# TLE5012B.net
KiCad netlist of a schematic drawn in Altium Designer
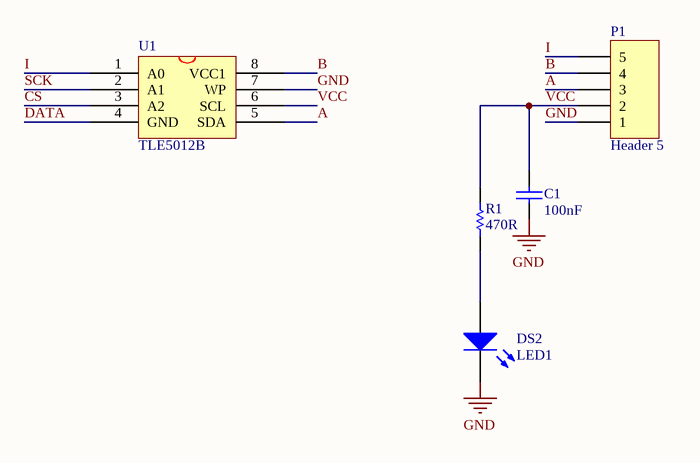
[diagram p0: TLE5012B.SchDoc]

(export (version "E")
  (design (tool "Eeschema 10.0.6"))
  (components
    (comp (ref "C1")
      (value "100nF")
      (footprint "C 0402")
      (description "Capacitor")
      (fields (field (name "PUBLISHER") "Altium Limited"))
      (libsource (lib "Miscellaneous Devices") (part "CAP"))
    )
    (comp (ref "DS2")
      (value "LED1")
      (footprint "SMDLED")
      (description "Typical RED, GREEN, YELLOW, AMBER GaAs LED")
      (fields (field (name "PUBLISHER") "Altium Limited"))
      (libsource (lib "EXPLORER") (part "LED2"))
    )
    (comp (ref "P1")
      (value "Header 5")
      (footprint "PH1.25_5")
      (description "Header, 5-Pin")
      (fields (field (name "PUBLISHER") "Altium Limited"))
      (libsource (lib "Miscellaneous Connectors") (part "Header 5"))
    )
    (comp (ref "R1")
      (value "470R")
      (footprint "R 0402")
      (description "0603")
      (libsource (lib "stm32f429i") (part "Res2"))
    )
    (comp (ref "U1") (value "TLE5012B") (footprint "SOP-8") (libsource (lib "EXPLORER") (part "24C256")))
  )
  (nets
    (net (code "1") (name "/A") (class "Default")
      (node (ref "P1") (pin "3") (pinfunction "3_3") (pintype "passive"))
      (node (ref "U1") (pin "5") (pinfunction "SDA_5") (pintype "passive"))
    )
    (net (code "2") (name "/B") (class "Default")
      (node (ref "P1") (pin "4") (pinfunction "4_4") (pintype "passive"))
      (node (ref "U1") (pin "8") (pinfunction "VCC1_8") (pintype "passive"))
    )
    (net (code "3") (name "/CS") (class "Default")
      (node (ref "U1") (pin "3") (pinfunction "A2_3") (pintype "passive"))
    )
    (net (code "4") (name "/DATA") (class "Default")
      (node (ref "U1") (pin "4") (pinfunction "GND_4") (pintype "passive"))
    )
    (net (code "5") (name "/I") (class "Default")
      (node (ref "P1") (pin "5") (pinfunction "5_5") (pintype "passive"))
      (node (ref "U1") (pin "1") (pinfunction "A0_1") (pintype "passive"))
    )
    (net (code "6") (name "/SCK") (class "Default")
      (node (ref "U1") (pin "2") (pinfunction "A1_2") (pintype "passive"))
    )
    (net (code "7") (name "/VCC") (class "Default")
      (node (ref "C1") (pin "1") (pinfunction "1_1") (pintype "passive"))
      (node (ref "P1") (pin "2") (pinfunction "2_2") (pintype "passive"))
      (node (ref "R1") (pin "1") (pinfunction "1_1") (pintype "passive"))
      (node (ref "U1") (pin "6") (pinfunction "SCL_6") (pintype "passive"))
    )
    (net (code "8") (name "GND") (class "Default")
      (node (ref "C1") (pin "2") (pinfunction "2_2") (pintype "passive"))
      (node (ref "DS2") (pin "2") (pinfunction "K_2") (pintype "passive"))
      (node (ref "P1") (pin "1") (pinfunction "1_1") (pintype "passive"))
      (node (ref "U1") (pin "7") (pinfunction "WP_7") (pintype "passive"))
    )
    (net (code "9") (name "Net-(DS2-A)") (class "Default")
      (node (ref "DS2") (pin "1") (pinfunction "A_1") (pintype "passive"))
      (node (ref "R1") (pin "2") (pinfunction "2_2") (pintype "passive"))
    )
  )
)
